# USB-RS485_A2.net
KiCad netlist of a schematic drawn in Altium Designer
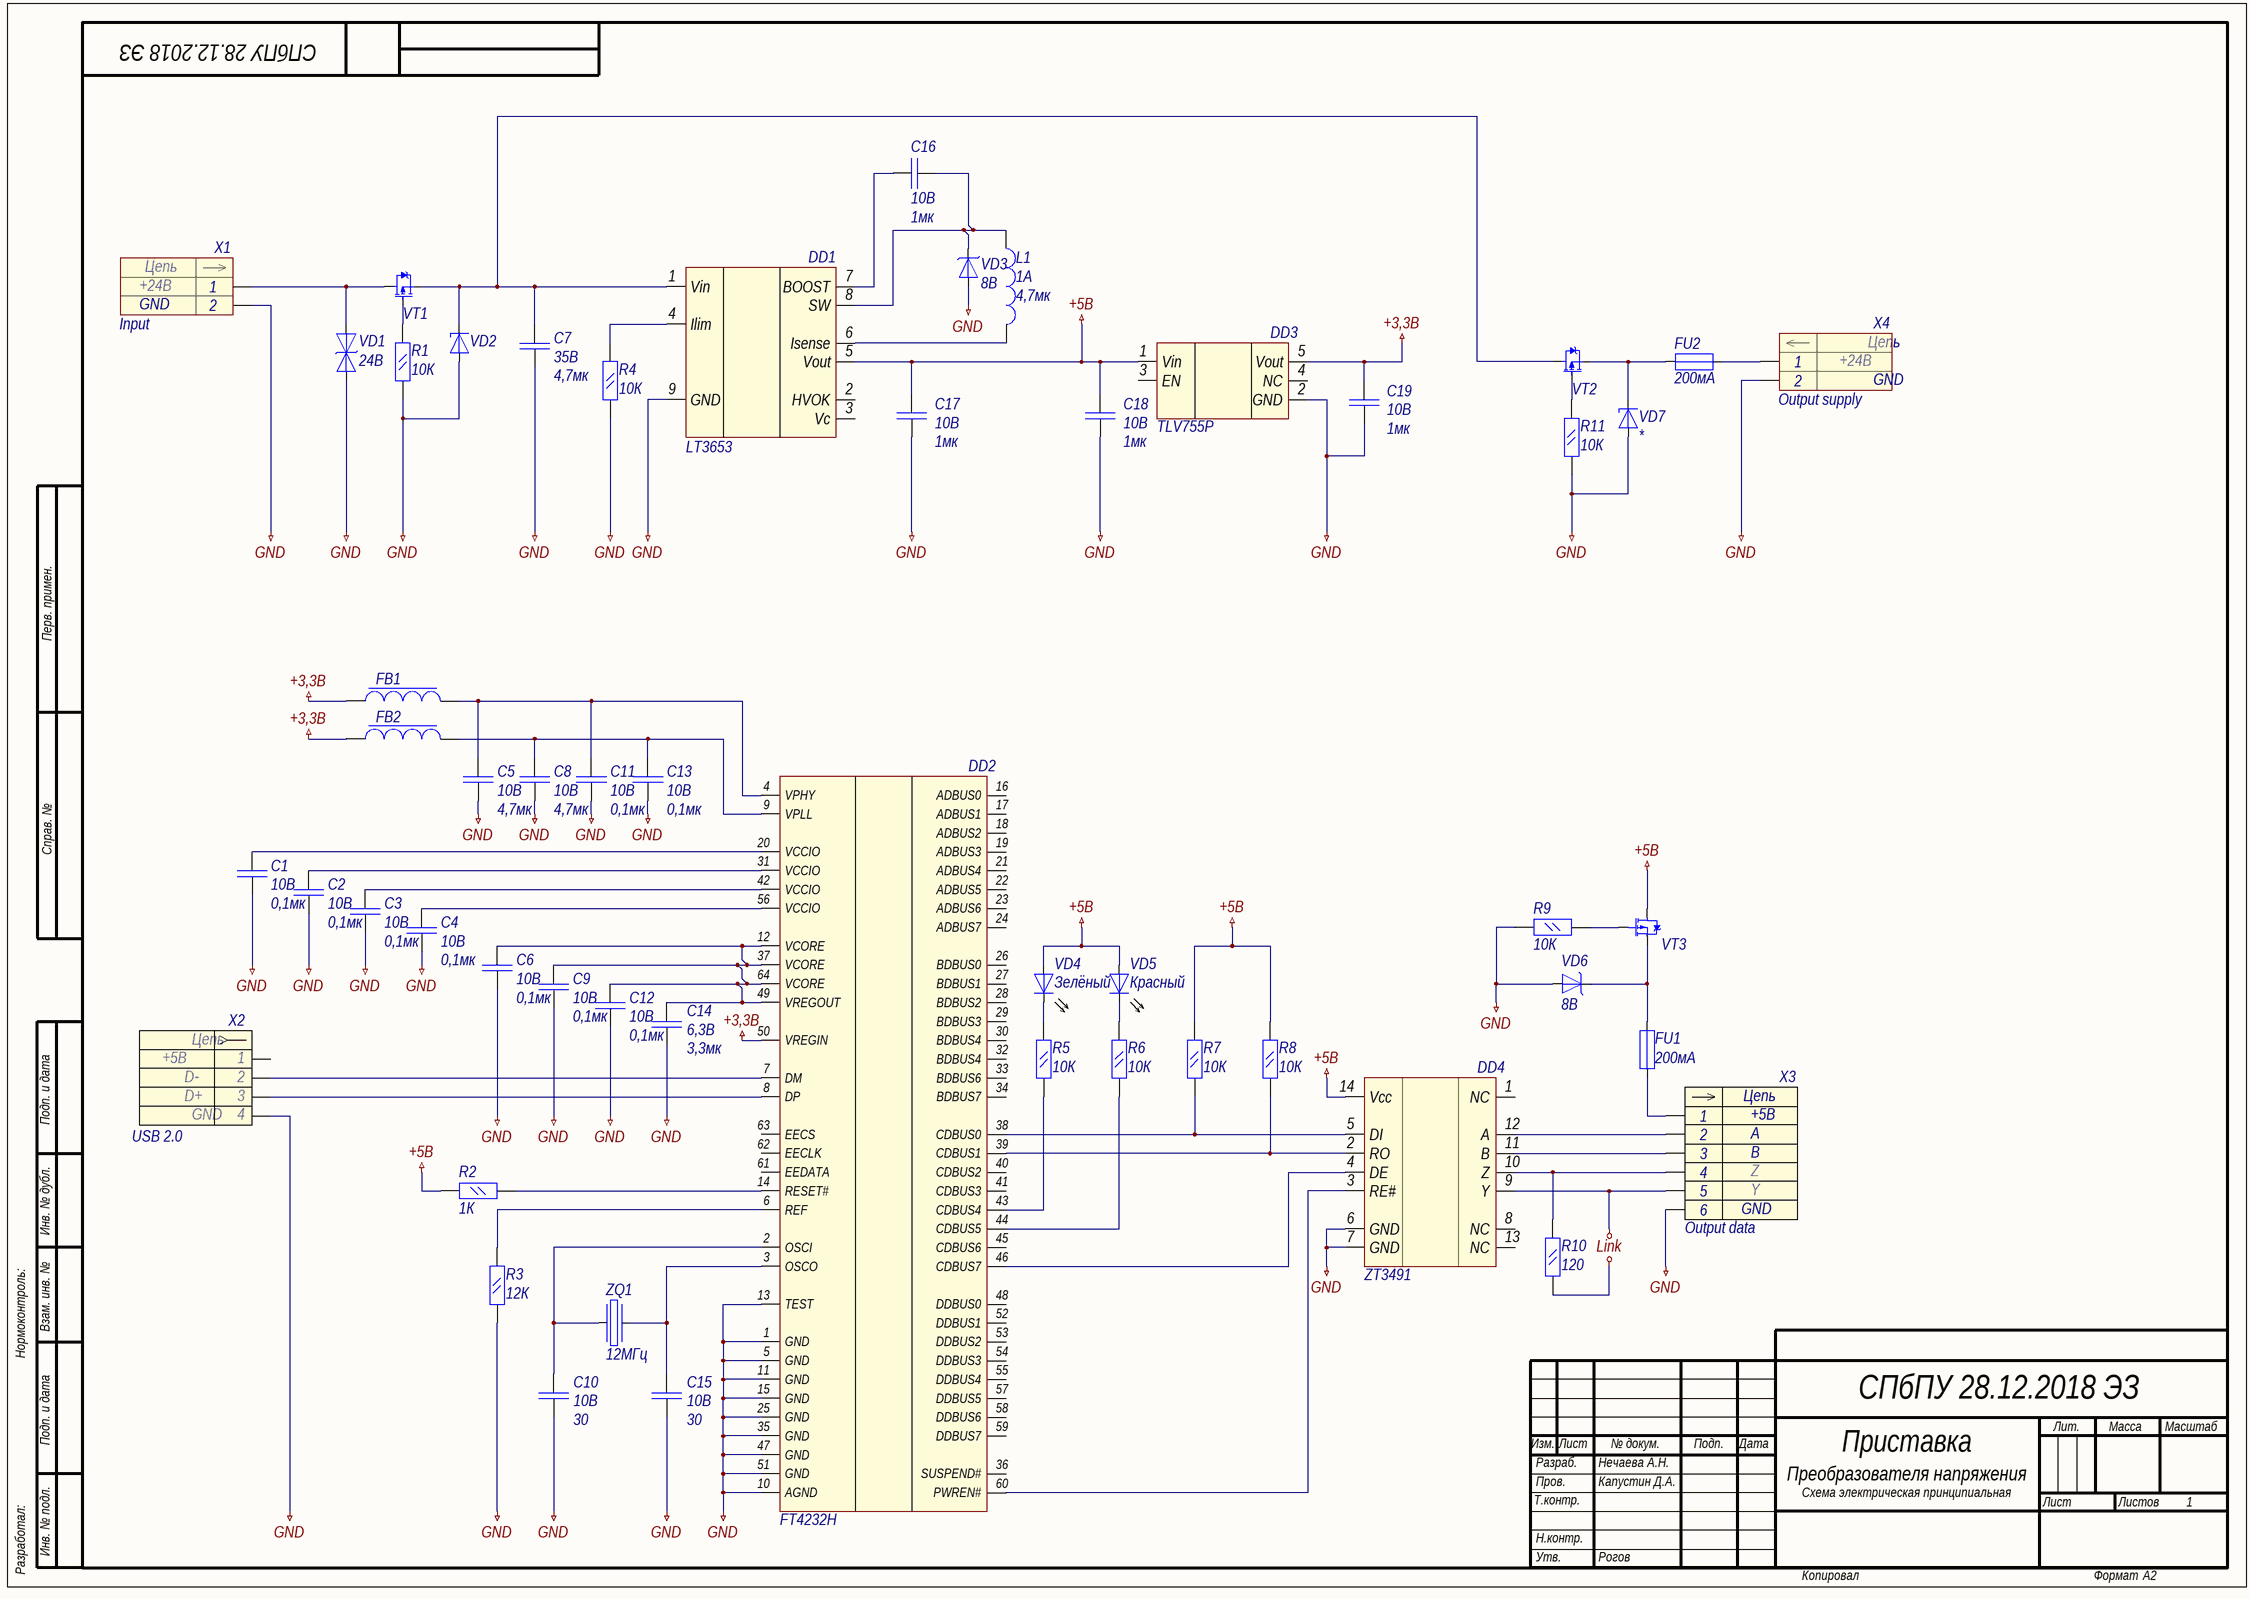
[diagram p0: USB-RS485_A2.SchDoc]

(export (version "E")
  (design (tool "Eeschema 10.0.6"))
  (components
    (comp (ref "C1")
      (value "Capacitor")
      (footprint "CH0402C")
      (fields (field (name "VOLTAGE") "10В") (field (name "CAPACITANCE") "0,1мк"))
      (libsource (lib "GOST_Capacitors") (part "Capacitor"))
    )
    (comp (ref "C2")
      (value "Capacitor")
      (footprint "CH0402C")
      (fields (field (name "VOLTAGE") "10В") (field (name "CAPACITANCE") "0,1мк"))
      (libsource (lib "GOST_Capacitors") (part "Capacitor"))
    )
    (comp (ref "C3")
      (value "Capacitor")
      (footprint "CH0402C")
      (fields (field (name "VOLTAGE") "10В") (field (name "CAPACITANCE") "0,1мк"))
      (libsource (lib "GOST_Capacitors") (part "Capacitor"))
    )
    (comp (ref "C4")
      (value "Capacitor")
      (footprint "CH0402C")
      (fields (field (name "VOLTAGE") "10В") (field (name "CAPACITANCE") "0,1мк"))
      (libsource (lib "GOST_Capacitors") (part "Capacitor"))
    )
    (comp (ref "C5")
      (value "Capacitor")
      (footprint "CH0402C")
      (fields (field (name "VOLTAGE") "10В") (field (name "CAPACITANCE") "4,7мк"))
      (libsource (lib "GOST_Capacitors") (part "Capacitor"))
    )
    (comp (ref "C6")
      (value "Capacitor")
      (footprint "CH0402C")
      (fields (field (name "VOLTAGE") "10В") (field (name "CAPACITANCE") "0,1мк"))
      (libsource (lib "GOST_Capacitors") (part "Capacitor"))
    )
    (comp (ref "C7")
      (value "Capacitor")
      (footprint "CH0603C")
      (fields (field (name "VOLTAGE") "35В") (field (name "CAPACITANCE") "4,7мк"))
      (libsource (lib "GOST_Capacitors") (part "Capacitor"))
    )
    (comp (ref "C8")
      (value "Capacitor")
      (footprint "CH0402C")
      (fields (field (name "VOLTAGE") "10В") (field (name "CAPACITANCE") "4,7мк"))
      (libsource (lib "GOST_Capacitors") (part "Capacitor"))
    )
    (comp (ref "C9")
      (value "Capacitor")
      (footprint "CH0402C")
      (fields (field (name "VOLTAGE") "10В") (field (name "CAPACITANCE") "0,1мк"))
      (libsource (lib "GOST_Capacitors") (part "Capacitor"))
    )
    (comp (ref "C10")
      (value "Capacitor")
      (footprint "CH0201C")
      (fields (field (name "VOLTAGE") "10В") (field (name "CAPACITANCE") "30"))
      (libsource (lib "GOST_Capacitors") (part "Capacitor"))
    )
    (comp (ref "C11")
      (value "Capacitor")
      (footprint "CH0402C")
      (fields (field (name "VOLTAGE") "10В") (field (name "CAPACITANCE") "0,1мк"))
      (libsource (lib "GOST_Capacitors") (part "Capacitor"))
    )
    (comp (ref "C12")
      (value "Capacitor")
      (footprint "CH0402C")
      (fields (field (name "VOLTAGE") "10В") (field (name "CAPACITANCE") "0,1мк"))
      (libsource (lib "GOST_Capacitors") (part "Capacitor"))
    )
    (comp (ref "C13")
      (value "Capacitor")
      (footprint "CH0402C")
      (fields (field (name "VOLTAGE") "10В") (field (name "CAPACITANCE") "0,1мк"))
      (libsource (lib "GOST_Capacitors") (part "Capacitor"))
    )
    (comp (ref "C14")
      (value "Capacitor")
      (footprint "CH0402C")
      (fields (field (name "VOLTAGE") "6,3В") (field (name "CAPACITANCE") "3,3мк"))
      (libsource (lib "GOST_Capacitors") (part "Capacitor"))
    )
    (comp (ref "C15")
      (value "Capacitor")
      (footprint "CH0201C")
      (fields (field (name "VOLTAGE") "10В") (field (name "CAPACITANCE") "30"))
      (libsource (lib "GOST_Capacitors") (part "Capacitor"))
    )
    (comp (ref "C16")
      (value "Capacitor")
      (footprint "CH0201C")
      (fields (field (name "VOLTAGE") "10В") (field (name "CAPACITANCE") "1мк"))
      (libsource (lib "GOST_Capacitors") (part "Capacitor"))
    )
    (comp (ref "C17")
      (value "Capacitor")
      (footprint "CH0201C")
      (fields (field (name "VOLTAGE") "10В") (field (name "CAPACITANCE") "1мк"))
      (libsource (lib "GOST_Capacitors") (part "Capacitor"))
    )
    (comp (ref "C18")
      (value "Capacitor")
      (footprint "CH0201C")
      (fields (field (name "VOLTAGE") "10В") (field (name "CAPACITANCE") "1мк"))
      (libsource (lib "GOST_Capacitors") (part "Capacitor"))
    )
    (comp (ref "C19")
      (value "Capacitor")
      (footprint "CH0201C")
      (fields (field (name "VOLTAGE") "10В") (field (name "CAPACITANCE") "1мк"))
      (libsource (lib "GOST_Capacitors") (part "Capacitor"))
    )
    (comp (ref "DD1")
      (value "LT3653")
      (footprint "LT3653")
      (description "7.5~30 to 5")
      (libsource (lib "GOST_lib_devices") (part "LT3653"))
    )
    (comp (ref "DD2")
      (value "FT4232H")
      (footprint "FT4232")
      (description "Ann")
      (libsource (lib "GOST_lib_devices") (part "FT4232H"))
    )
    (comp (ref "DD3")
      (value "TLV755P")
      (footprint "SOT23-5")
      (libsource (lib "GOST_lib_devices") (part "LDO +3.3V"))
    )
    (comp (ref "DD4")
      (value "ZT3491")
      (footprint "ZT3485E")
      (description "UART - RS485")
      (libsource (lib "GOST_lib_devices") (part "ZT3491"))
    )
    (comp (ref "FB1")
      (value "Ferrite bead")
      (footprint "CH0805F")
      (libsource (lib "GOST_Inductors") (part "Ferrite bead"))
    )
    (comp (ref "FB2")
      (value "Ferrite bead")
      (footprint "CH0805F")
      (libsource (lib "GOST_Inductors") (part "Ferrite bead"))
    )
    (comp (ref "FU1")
      (value "200мА")
      (footprint "CH0402R")
      (fields (field (name "Comment") "Fuse"))
      (libsource (lib "") (part "Fuse_1"))
    )
    (comp (ref "FU2")
      (value "200мА")
      (footprint "CH0402R")
      (fields (field (name "Comment") "Fuse"))
      (libsource (lib "GOST_Miscelanuious") (part "Fuse"))
    )
    (comp (ref "L1")
      (value "Inductor")
      (footprint "CH0805L")
      (fields (field (name "MAX CURRENT") "1А") (field (name "INDUCTANCE") "4,7мк"))
      (libsource (lib "GOST_Inductors") (part "Inductor"))
    )
    (comp (ref "R1")
      (value "Res_0.125")
      (footprint "CH0402R")
      (fields (field (name "IMPEDANCE") "10К"))
      (libsource (lib "GOST_Resistors") (part "Res_0.125"))
    )
    (comp (ref "R2")
      (value "Res_0.125")
      (footprint "CH0402R")
      (fields (field (name "IMPEDANCE") "1К"))
      (libsource (lib "GOST_Resistors") (part "Res_0.125"))
    )
    (comp (ref "R3")
      (value "Res_0.125")
      (footprint "CH0805R")
      (fields (field (name "IMPEDANCE") "12К"))
      (libsource (lib "GOST_Resistors") (part "Res_0.125"))
    )
    (comp (ref "R4")
      (value "Res_0.125")
      (footprint "CH0402R")
      (fields (field (name "IMPEDANCE") "10К"))
      (libsource (lib "GOST_Resistors") (part "Res_0.125"))
    )
    (comp (ref "R5")
      (value "Res_0.125")
      (footprint "CH0402R")
      (fields (field (name "IMPEDANCE") "10К"))
      (libsource (lib "GOST_Resistors") (part "Res_0.125"))
    )
    (comp (ref "R6")
      (value "Res_0.125")
      (footprint "CH0402R")
      (fields (field (name "IMPEDANCE") "10К"))
      (libsource (lib "GOST_Resistors") (part "Res_0.125"))
    )
    (comp (ref "R7")
      (value "Res_0.125")
      (footprint "CH0402R")
      (fields (field (name "IMPEDANCE") "10К"))
      (libsource (lib "GOST_Resistors") (part "Res_0.125"))
    )
    (comp (ref "R8")
      (value "Res_0.125")
      (footprint "CH0402R")
      (fields (field (name "IMPEDANCE") "10К"))
      (libsource (lib "GOST_Resistors") (part "Res_0.125"))
    )
    (comp (ref "R9")
      (value "Res_0.125")
      (footprint "CH0402R")
      (fields (field (name "IMPEDANCE") "10К"))
      (libsource (lib "GOST_Resistors") (part "Res_0.125"))
    )
    (comp (ref "R10")
      (value "Res_0.125")
      (footprint "CH0402R")
      (fields (field (name "IMPEDANCE") "120"))
      (libsource (lib "GOST_Resistors") (part "Res_0.125"))
    )
    (comp (ref "R11")
      (value "Res_0.125")
      (footprint "CH0402R")
      (fields (field (name "IMPEDANCE") "10К"))
      (libsource (lib "GOST_Resistors") (part "Res_0.125"))
    )
    (comp (ref "VD1")
      (value "TVS-diod_simmetrical")
      (footprint "standard:SOD323")
      (fields (field (name "MANUFACTURER") "Torex Semiconductor") (field (name "THRESH_VOLTAGE") "24В"))
      (libsource (lib "GOST_Diodes") (part "TVS-diod_simmetrical"))
    )
    (comp (ref "VD2")
      (value "Diod Zener")
      (footprint "standard:SOD123")
      (libsource (lib "GOST_Diodes") (part "Diod Zener"))
    )
    (comp (ref "VD3")
      (value "TVS-diod_directed")
      (footprint "SOD123W")
      (fields (field (name "MANUFACTURER") "Nexperia") (field (name "CLAMPING_VOLTAGE") "8В"))
      (libsource (lib "GOST_Diodes") (part "TVS-diod_directed"))
    )
    (comp (ref "VD4")
      (value "Light_diod")
      (footprint "CH0201L")
      (fields (field (name "COLOR") "Зелёный"))
      (libsource (lib "GOST_Diodes") (part "Light_diod"))
    )
    (comp (ref "VD5")
      (value "Light_diod")
      (footprint "CH0201L")
      (fields (field (name "COLOR") "Красный"))
      (libsource (lib "GOST_Diodes") (part "Light_diod"))
    )
    (comp (ref "VD6")
      (value "TVS-diod_directed")
      (footprint "SOD123W")
      (fields (field (name "MANUFACTURER") "Nexperia") (field (name "CLAMPING_VOLTAGE") "8В"))
      (libsource (lib "GOST_Diodes") (part "TVS-diod_directed"))
    )
    (comp (ref "VD7")
      (value "Diod Zener")
      (footprint "standard:SOD123")
      (fields (field (name "THRESH_VOLTAGE") "*"))
      (libsource (lib "GOST_Diodes") (part "Diod Zener"))
    )
    (comp (ref "VT1")
      (value "P-Channel")
      (footprint "SOT23_132")
      (libsource (lib "GOST_Transistors") (part "P-Channel"))
    )
    (comp (ref "VT2")
      (value "P-Channel")
      (footprint "SOT23_132")
      (libsource (lib "GOST_Transistors") (part "P-Channel"))
    )
    (comp (ref "VT3") (value "*") (footprint "SOT23_132") (libsource (lib "") (part "P-Channel_1")))
    (comp (ref "X1")
      (value "Input")
      (footprint "CON: 163-179PH-EX")
      (fields (field (name "VCC") "+24В"))
      (libsource (lib "GOST_lib_connectors") (part "2_pins"))
    )
    (comp (ref "X2")
      (value "USB 2.0")
      (footprint "Integrated_Library:USB")
      (description "USB")
      (fields (field (name "MANUFACTURER") "TE Connectivity") (field (name "VCC") "+5В"))
      (libsource (lib "Connectors") (part "USB-A"))
    )
    (comp (ref "X3")
      (value "Output data")
      (footprint "CON: PBS-6")
      (fields
        (field (name "Z") "Z")
        (field (name "Y") "Y")
        (field (name "VCC") "+5В")
        (field (name "A") "A")
        (field (name "B") "B")
      )
      (libsource (lib "GOST_lib_connectors") (part "Full_Duplex_RS485"))
    )
    (comp (ref "X4")
      (value "Output supply")
      (footprint "CON: PBS-2")
      (fields (field (name "VCC") "+24В"))
      (libsource (lib "") (part "2_pins_1"))
    )
    (comp (ref "ZQ1")
      (value "12МГц")
      (footprint "OSC: 5032")
      (fields (field (name "Comment") "Oscillator"))
      (libsource (lib "GOST_Miscelanuious") (part "Oscillator"))
    )
  )
  (nets
    (net (code "1") (name "+3,3В") (class "Default")
      (node (ref "C19") (pin "1") (pinfunction "C1+_1") (pintype "power_in"))
      (node (ref "DD2") (pin "50") (pinfunction "VREGIN_50") (pintype "power_in"))
      (node (ref "DD3") (pin "5") (pinfunction "Vout_5") (pintype "power_in"))
      (node (ref "FB1") (pin "1") (pinfunction "C1-_1") (pintype "power_in"))
      (node (ref "FB2") (pin "1") (pinfunction "C1-_1") (pintype "power_in"))
    )
    (net (code "2") (name "+5В") (class "Default")
      (node (ref "C17") (pin "1") (pinfunction "C1+_1") (pintype "power_in"))
      (node (ref "C18") (pin "1") (pinfunction "C1+_1") (pintype "power_in"))
      (node (ref "DD1") (pin "5") (pinfunction "Vout_5") (pintype "power_in"))
      (node (ref "DD3") (pin "1") (pinfunction "Vin_1") (pintype "power_in"))
      (node (ref "DD4") (pin "14") (pinfunction "Vcc_14") (pintype "power_in"))
      (node (ref "R2") (pin "2") (pinfunction "2_2") (pintype "power_in"))
      (node (ref "R7") (pin "2") (pinfunction "2_2") (pintype "power_in"))
      (node (ref "R8") (pin "2") (pinfunction "2_2") (pintype "power_in"))
      (node (ref "VD4") (pin "1") (pinfunction "1_1") (pintype "passive"))
      (node (ref "VD5") (pin "1") (pinfunction "1_1") (pintype "passive"))
      (node (ref "VT3") (pin "2") (pinfunction "D_2") (pintype "passive"))
    )
    (net (code "3") (name "GND") (class "Default")
      (node (ref "C1") (pin "2") (pinfunction "C1-_2") (pintype "power_in"))
      (node (ref "C10") (pin "2") (pinfunction "C1-_2") (pintype "power_in"))
      (node (ref "C11") (pin "2") (pinfunction "C1-_2") (pintype "power_in"))
      (node (ref "C12") (pin "2") (pinfunction "C1-_2") (pintype "power_in"))
      (node (ref "C13") (pin "2") (pinfunction "C1-_2") (pintype "power_in"))
      (node (ref "C14") (pin "2") (pinfunction "C1-_2") (pintype "power_in"))
      (node (ref "C15") (pin "2") (pinfunction "C1-_2") (pintype "power_in"))
      (node (ref "C17") (pin "2") (pinfunction "C1-_2") (pintype "power_in"))
      (node (ref "C18") (pin "2") (pinfunction "C1-_2") (pintype "power_in"))
      (node (ref "C19") (pin "2") (pinfunction "C1-_2") (pintype "power_in"))
      (node (ref "C2") (pin "2") (pinfunction "C1-_2") (pintype "power_in"))
      (node (ref "C3") (pin "2") (pinfunction "C1-_2") (pintype "power_in"))
      (node (ref "C4") (pin "2") (pinfunction "C1-_2") (pintype "power_in"))
      (node (ref "C5") (pin "2") (pinfunction "C1-_2") (pintype "power_in"))
      (node (ref "C6") (pin "2") (pinfunction "C1-_2") (pintype "power_in"))
      (node (ref "C7") (pin "2") (pinfunction "C1-_2") (pintype "power_in"))
      (node (ref "C8") (pin "2") (pinfunction "C1-_2") (pintype "power_in"))
      (node (ref "C9") (pin "2") (pinfunction "C1-_2") (pintype "power_in"))
      (node (ref "DD1") (pin "9") (pinfunction "GND_9") (pintype "power_in"))
      (node (ref "DD2") (pin "1") (pinfunction "GND_1") (pintype "power_in"))
      (node (ref "DD2") (pin "10") (pinfunction "AGND_10") (pintype "power_in"))
      (node (ref "DD2") (pin "11") (pinfunction "GND_11") (pintype "power_in"))
      (node (ref "DD2") (pin "13") (pinfunction "TEST_13") (pintype "power_in"))
      (node (ref "DD2") (pin "15") (pinfunction "GND_15") (pintype "power_in"))
      (node (ref "DD2") (pin "25") (pinfunction "GND_25") (pintype "power_in"))
      (node (ref "DD2") (pin "35") (pinfunction "GND_35") (pintype "power_in"))
      (node (ref "DD2") (pin "47") (pinfunction "GND_47") (pintype "power_in"))
      (node (ref "DD2") (pin "5") (pinfunction "GND_5") (pintype "power_in"))
      (node (ref "DD2") (pin "51") (pinfunction "GND_51") (pintype "power_in"))
      (node (ref "DD3") (pin "2") (pinfunction "GND_2") (pintype "power_in"))
      (node (ref "DD4") (pin "6") (pinfunction "GND_6") (pintype "power_in"))
      (node (ref "DD4") (pin "7") (pinfunction "GND_7") (pintype "power_in"))
      (node (ref "R1") (pin "1") (pinfunction "1_1") (pintype "power_in"))
      (node (ref "R11") (pin "1") (pinfunction "1_1") (pintype "power_in"))
      (node (ref "R3") (pin "1") (pinfunction "1_1") (pintype "power_in"))
      (node (ref "R4") (pin "1") (pinfunction "1_1") (pintype "power_in"))
      (node (ref "R9") (pin "2") (pinfunction "2_2") (pintype "power_in"))
      (node (ref "VD1") (pin "1") (pinfunction "A_1") (pintype "passive"))
      (node (ref "VD2") (pin "1") (pinfunction "A_1") (pintype "passive"))
      (node (ref "VD3") (pin "1") (pinfunction "A_1") (pintype "passive"))
      (node (ref "VD6") (pin "1") (pinfunction "A_1") (pintype "passive"))
      (node (ref "VD7") (pin "1") (pinfunction "A_1") (pintype "passive"))
      (node (ref "X1") (pin "2") (pinfunction "2_2") (pintype "passive"))
      (node (ref "X2") (pin "4") (pinfunction "4_4") (pintype "passive"))
      (node (ref "X3") (pin "6") (pinfunction "6_6") (pintype "passive"))
      (node (ref "X4") (pin "2") (pinfunction "2_2") (pintype "passive"))
    )
    (net (code "4") (name "Link") (class "Default")
      (node (ref "DD4") (pin "9") (pinfunction "Y_9") (pintype "power_in"))
      (node (ref "R10") (pin "1") (pinfunction "1_1") (pintype "power_in"))
      (node (ref "X3") (pin "5") (pinfunction "5_5") (pintype "passive"))
    )
    (net (code "5") (name "Net-(C1-C1+)") (class "Default")
      (node (ref "C1") (pin "1") (pinfunction "C1+_1") (pintype "power_in"))
      (node (ref "DD2") (pin "20") (pinfunction "VCCIO_20") (pintype "power_in"))
    )
    (net (code "6") (name "Net-(C2-C1+)") (class "Default")
      (node (ref "C2") (pin "1") (pinfunction "C1+_1") (pintype "power_in"))
      (node (ref "DD2") (pin "31") (pinfunction "VCCIO_31") (pintype "power_in"))
    )
    (net (code "7") (name "Net-(C3-C1+)") (class "Default")
      (node (ref "C3") (pin "1") (pinfunction "C1+_1") (pintype "power_in"))
      (node (ref "DD2") (pin "42") (pinfunction "VCCIO_42") (pintype "power_in"))
    )
    (net (code "8") (name "Net-(C4-C1+)") (class "Default")
      (node (ref "C4") (pin "1") (pinfunction "C1+_1") (pintype "power_in"))
      (node (ref "DD2") (pin "56") (pinfunction "VCCIO_56") (pintype "power_in"))
    )
    (net (code "9") (name "Net-(C7-C1+)") (class "Default")
      (node (ref "C7") (pin "1") (pinfunction "C1+_1") (pintype "power_in"))
      (node (ref "DD1") (pin "1") (pinfunction "Vin_1") (pintype "power_in"))
      (node (ref "VD2") (pin "2") (pinfunction "C_2") (pintype "passive"))
      (node (ref "VT1") (pin "3") (pinfunction "S_3") (pintype "passive"))
      (node (ref "VT2") (pin "2") (pinfunction "D_2") (pintype "passive"))
    )
    (net (code "10") (name "Net-(C10-C1+)") (class "Default")
      (node (ref "C10") (pin "1") (pinfunction "C1+_1") (pintype "power_in"))
      (node (ref "DD2") (pin "2") (pinfunction "OSCI_2") (pintype "power_in"))
      (node (ref "ZQ1") (pin "1") (pinfunction "1_1") (pintype "passive"))
    )
    (net (code "11") (name "Net-(C11-C1+)") (class "Default")
      (node (ref "C11") (pin "1") (pinfunction "C1+_1") (pintype "power_in"))
      (node (ref "C5") (pin "1") (pinfunction "C1+_1") (pintype "power_in"))
      (node (ref "DD2") (pin "4") (pinfunction "VPHY_4") (pintype "power_in"))
      (node (ref "FB1") (pin "2") (pinfunction "14_2") (pintype "power_in"))
    )
    (net (code "12") (name "Net-(C12-C1+)") (class "Default")
      (node (ref "C12") (pin "1") (pinfunction "C1+_1") (pintype "power_in"))
      (node (ref "C14") (pin "1") (pinfunction "C1+_1") (pintype "power_in"))
      (node (ref "C6") (pin "1") (pinfunction "C1+_1") (pintype "power_in"))
      (node (ref "C9") (pin "1") (pinfunction "C1+_1") (pintype "power_in"))
      (node (ref "DD2") (pin "12") (pinfunction "VCORE_12") (pintype "power_in"))
      (node (ref "DD2") (pin "37") (pinfunction "VCORE_37") (pintype "power_in"))
      (node (ref "DD2") (pin "49") (pinfunction "VREGOUT_49") (pintype "power_in"))
      (node (ref "DD2") (pin "64") (pinfunction "VCORE_64") (pintype "power_in"))
    )
    (net (code "13") (name "Net-(C13-C1+)") (class "Default")
      (node (ref "C13") (pin "1") (pinfunction "C1+_1") (pintype "power_in"))
      (node (ref "C8") (pin "1") (pinfunction "C1+_1") (pintype "power_in"))
      (node (ref "DD2") (pin "9") (pinfunction "VPLL_9") (pintype "power_in"))
      (node (ref "FB2") (pin "2") (pinfunction "14_2") (pintype "power_in"))
    )
    (net (code "14") (name "Net-(C15-C1+)") (class "Default")
      (node (ref "C15") (pin "1") (pinfunction "C1+_1") (pintype "power_in"))
      (node (ref "DD2") (pin "3") (pinfunction "OSCO_3") (pintype "power_in"))
      (node (ref "ZQ1") (pin "3") (pinfunction "3_3") (pintype "passive"))
    )
    (net (code "15") (name "Net-(C16-C1+)") (class "Default")
      (node (ref "C16") (pin "1") (pinfunction "C1+_1") (pintype "power_in"))
      (node (ref "DD1") (pin "7") (pinfunction "BOOST_7") (pintype "power_in"))
    )
    (net (code "16") (name "Net-(C16-C1-)") (class "Default")
      (node (ref "C16") (pin "2") (pinfunction "C1-_2") (pintype "power_in"))
      (node (ref "DD1") (pin "8") (pinfunction "SW_8") (pintype "power_in"))
      (node (ref "L1") (pin "1") (pinfunction "1_1") (pintype "power_in"))
      (node (ref "VD3") (pin "2") (pinfunction "C_2") (pintype "passive"))
    )
    (net (code "17") (name "Net-(DD1-Ilim)") (class "Default")
      (node (ref "DD1") (pin "4") (pinfunction "Ilim_4") (pintype "power_in"))
      (node (ref "R4") (pin "2") (pinfunction "2_2") (pintype "power_in"))
    )
    (net (code "18") (name "Net-(DD1-Isense)") (class "Default")
      (node (ref "DD1") (pin "6") (pinfunction "Isense_6") (pintype "power_in"))
      (node (ref "L1") (pin "2") (pinfunction "2_2") (pintype "power_in"))
    )
    (net (code "19") (name "Net-(DD2-CDBUS0)") (class "Default")
      (node (ref "DD2") (pin "38") (pinfunction "CDBUS0_38") (pintype "power_in"))
      (node (ref "DD4") (pin "5") (pinfunction "DI_5") (pintype "power_in"))
      (node (ref "R7") (pin "1") (pinfunction "1_1") (pintype "power_in"))
    )
    (net (code "20") (name "Net-(DD2-CDBUS1)") (class "Default")
      (node (ref "DD2") (pin "39") (pinfunction "CDBUS1_39") (pintype "power_in"))
      (node (ref "DD4") (pin "2") (pinfunction "RO_2") (pintype "power_in"))
      (node (ref "R8") (pin "1") (pinfunction "1_1") (pintype "power_in"))
    )
    (net (code "21") (name "Net-(DD2-CDBUS4)") (class "Default")
      (node (ref "DD2") (pin "43") (pinfunction "CDBUS4_43") (pintype "power_in"))
      (node (ref "R5") (pin "1") (pinfunction "1_1") (pintype "power_in"))
    )
    (net (code "22") (name "Net-(DD2-CDBUS5)") (class "Default")
      (node (ref "DD2") (pin "44") (pinfunction "CDBUS5_44") (pintype "power_in"))
      (node (ref "R6") (pin "1") (pinfunction "1_1") (pintype "power_in"))
    )
    (net (code "23") (name "Net-(DD2-CDBUS7)") (class "Default")
      (node (ref "DD2") (pin "46") (pinfunction "CDBUS7_46") (pintype "power_in"))
      (node (ref "DD4") (pin "4") (pinfunction "DE_4") (pintype "power_in"))
    )
    (net (code "24") (name "Net-(DD2-DM)") (class "Default")
      (node (ref "DD2") (pin "7") (pinfunction "DM_7") (pintype "power_in"))
      (node (ref "X2") (pin "2") (pinfunction "2_2") (pintype "passive"))
    )
    (net (code "25") (name "Net-(DD2-DP)") (class "Default")
      (node (ref "DD2") (pin "8") (pinfunction "DP_8") (pintype "power_in"))
      (node (ref "X2") (pin "3") (pinfunction "3_3") (pintype "passive"))
    )
    (net (code "26") (name "Net-(DD2-PWREN#)") (class "Default")
      (node (ref "DD2") (pin "60") (pinfunction "PWREN#_60") (pintype "power_in"))
      (node (ref "DD4") (pin "3") (pinfunction "RE#_3") (pintype "power_in"))
    )
    (net (code "27") (name "Net-(DD2-REF)") (class "Default")
      (node (ref "DD2") (pin "6") (pinfunction "REF_6") (pintype "power_in"))
      (node (ref "R3") (pin "2") (pinfunction "2_2") (pintype "power_in"))
    )
    (net (code "28") (name "Net-(DD2-RESET#)") (class "Default")
      (node (ref "DD2") (pin "14") (pinfunction "RESET#_14") (pintype "power_in"))
      (node (ref "R2") (pin "1") (pinfunction "1_1") (pintype "power_in"))
    )
    (net (code "29") (name "Net-(DD4-A)") (class "Default")
      (node (ref "DD4") (pin "12") (pinfunction "A_12") (pintype "power_in"))
      (node (ref "X3") (pin "2") (pinfunction "2_2") (pintype "passive"))
    )
    (net (code "30") (name "Net-(DD4-B)") (class "Default")
      (node (ref "DD4") (pin "11") (pinfunction "B_11") (pintype "power_in"))
      (node (ref "X3") (pin "3") (pinfunction "3_3") (pintype "passive"))
    )
    (net (code "31") (name "Net-(DD4-Z)") (class "Default")
      (node (ref "DD4") (pin "10") (pinfunction "Z_10") (pintype "power_in"))
      (node (ref "R10") (pin "2") (pinfunction "2_2") (pintype "power_in"))
      (node (ref "X3") (pin "4") (pinfunction "4_4") (pintype "passive"))
    )
    (net (code "32") (name "Net-(FU1-Pad1)") (class "Default")
      (node (ref "FU1") (pin "1") (pinfunction "1_1") (pintype "passive"))
      (node (ref "X3") (pin "1") (pinfunction "1_1") (pintype "passive"))
    )
    (net (code "33") (name "Net-(FU2-Pad2)") (class "Default")
      (node (ref "FU2") (pin "2") (pinfunction "2_2") (pintype "passive"))
      (node (ref "X4") (pin "1") (pinfunction "1_1") (pintype "passive"))
    )
    (net (code "34") (name "Net-(R5-Pad2)") (class "Default")
      (node (ref "R5") (pin "2") (pinfunction "2_2") (pintype "power_in"))
      (node (ref "VD4") (pin "2") (pinfunction "2_2") (pintype "passive"))
    )
    (net (code "35") (name "Net-(R6-Pad2)") (class "Default")
      (node (ref "R6") (pin "2") (pinfunction "2_2") (pintype "power_in"))
      (node (ref "VD5") (pin "2") (pinfunction "2_2") (pintype "passive"))
    )
    (net (code "36") (name "Net-(VD1-C)") (class "Default")
      (node (ref "VD1") (pin "2") (pinfunction "C_2") (pintype "passive"))
      (node (ref "VT1") (pin "2") (pinfunction "D_2") (pintype "passive"))
      (node (ref "X1") (pin "1") (pinfunction "1_1") (pintype "passive"))
    )
    (net (code "37") (name "Net-(VD6-C)") (class "Default")
      (node (ref "FU1") (pin "2") (pinfunction "2_2") (pintype "passive"))
      (node (ref "VD6") (pin "2") (pinfunction "C_2") (pintype "passive"))
      (node (ref "VT3") (pin "3") (pinfunction "S_3") (pintype "passive"))
    )
    (net (code "38") (name "Net-(VD7-C)") (class "Default")
      (node (ref "FU2") (pin "1") (pinfunction "1_1") (pintype "passive"))
      (node (ref "VD7") (pin "2") (pinfunction "C_2") (pintype "passive"))
      (node (ref "VT2") (pin "3") (pinfunction "S_3") (pintype "passive"))
    )
    (net (code "39") (name "Net-(VT1-G)") (class "Default")
      (node (ref "R1") (pin "2") (pinfunction "2_2") (pintype "power_in"))
      (node (ref "VT1") (pin "1") (pinfunction "G_1") (pintype "passive"))
    )
    (net (code "40") (name "Net-(VT2-G)") (class "Default")
      (node (ref "R11") (pin "2") (pinfunction "2_2") (pintype "power_in"))
      (node (ref "VT2") (pin "1") (pinfunction "G_1") (pintype "passive"))
    )
    (net (code "41") (name "Net-(VT3-G)") (class "Default")
      (node (ref "R9") (pin "1") (pinfunction "1_1") (pintype "power_in"))
      (node (ref "VT3") (pin "1") (pinfunction "G_1") (pintype "passive"))
    )
    (net (code "42") (name "unconnected-(DD1-HVOK-Pad2)") (class "Default")
      (node (ref "DD1") (pin "2") (pinfunction "HVOK_2") (pintype "power_in"))
    )
    (net (code "43") (name "unconnected-(DD1-Vc-Pad3)") (class "Default")
      (node (ref "DD1") (pin "3") (pinfunction "Vc_3") (pintype "power_in"))
    )
    (net (code "44") (name "unconnected-(DD2-ADBUS0-Pad16)") (class "Default")
      (node (ref "DD2") (pin "16") (pinfunction "ADBUS0_16") (pintype "power_in"))
    )
    (net (code "45") (name "unconnected-(DD2-ADBUS1-Pad17)") (class "Default")
      (node (ref "DD2") (pin "17") (pinfunction "ADBUS1_17") (pintype "power_in"))
    )
    (net (code "46") (name "unconnected-(DD2-ADBUS2-Pad18)") (class "Default")
      (node (ref "DD2") (pin "18") (pinfunction "ADBUS2_18") (pintype "power_in"))
    )
    (net (code "47") (name "unconnected-(DD2-ADBUS3-Pad19)") (class "Default")
      (node (ref "DD2") (pin "19") (pinfunction "ADBUS3_19") (pintype "power_in"))
    )
    (net (code "48") (name "unconnected-(DD2-ADBUS4-Pad21)") (class "Default")
      (node (ref "DD2") (pin "21") (pinfunction "ADBUS4_21") (pintype "power_in"))
    )
    (net (code "49") (name "unconnected-(DD2-ADBUS5-Pad22)") (class "Default")
      (node (ref "DD2") (pin "22") (pinfunction "ADBUS5_22") (pintype "power_in"))
    )
    (net (code "50") (name "unconnected-(DD2-ADBUS6-Pad23)") (class "Default")
      (node (ref "DD2") (pin "23") (pinfunction "ADBUS6_23") (pintype "power_in"))
    )
    (net (code "51") (name "unconnected-(DD2-ADBUS7-Pad24)") (class "Default")
      (node (ref "DD2") (pin "24") (pinfunction "ADBUS7_24") (pintype "power_in"))
    )
    (net (code "52") (name "unconnected-(DD2-BDBUS0-Pad26)") (class "Default")
      (node (ref "DD2") (pin "26") (pinfunction "BDBUS0_26") (pintype "power_in"))
    )
    (net (code "53") (name "unconnected-(DD2-BDBUS1-Pad27)") (class "Default")
      (node (ref "DD2") (pin "27") (pinfunction "BDBUS1_27") (pintype "power_in"))
    )
    (net (code "54") (name "unconnected-(DD2-BDBUS2-Pad28)") (class "Default")
      (node (ref "DD2") (pin "28") (pinfunction "BDBUS2_28") (pintype "power_in"))
    )
    (net (code "55") (name "unconnected-(DD2-BDBUS3-Pad29)") (class "Default")
      (node (ref "DD2") (pin "29") (pinfunction "BDBUS3_29") (pintype "power_in"))
    )
    (net (code "56") (name "unconnected-(DD2-BDBUS4-Pad30)") (class "Default")
      (node (ref "DD2") (pin "30") (pinfunction "BDBUS4_30") (pintype "power_in"))
    )
    (net (code "57") (name "unconnected-(DD2-BDBUS4-Pad32)") (class "Default")
      (node (ref "DD2") (pin "32") (pinfunction "BDBUS4_32") (pintype "power_in"))
    )
    (net (code "58") (name "unconnected-(DD2-BDBUS6-Pad33)") (class "Default")
      (node (ref "DD2") (pin "33") (pinfunction "BDBUS6_33") (pintype "power_in"))
    )
    (net (code "59") (name "unconnected-(DD2-BDBUS7-Pad34)") (class "Default")
      (node (ref "DD2") (pin "34") (pinfunction "BDBUS7_34") (pintype "power_in"))
    )
    (net (code "60") (name "unconnected-(DD2-CDBUS2-Pad40)") (class "Default")
      (node (ref "DD2") (pin "40") (pinfunction "CDBUS2_40") (pintype "power_in"))
    )
    (net (code "61") (name "unconnected-(DD2-CDBUS3-Pad41)") (class "Default")
      (node (ref "DD2") (pin "41") (pinfunction "CDBUS3_41") (pintype "power_in"))
    )
    (net (code "62") (name "unconnected-(DD2-CDBUS6-Pad45)") (class "Default")
      (node (ref "DD2") (pin "45") (pinfunction "CDBUS6_45") (pintype "power_in"))
    )
    (net (code "63") (name "unconnected-(DD2-DDBUS0-Pad48)") (class "Default")
      (node (ref "DD2") (pin "48") (pinfunction "DDBUS0_48") (pintype "power_in"))
    )
    (net (code "64") (name "unconnected-(DD2-DDBUS1-Pad52)") (class "Default")
      (node (ref "DD2") (pin "52") (pinfunction "DDBUS1_52") (pintype "power_in"))
    )
    (net (code "65") (name "unconnected-(DD2-DDBUS2-Pad53)") (class "Default")
      (node (ref "DD2") (pin "53") (pinfunction "DDBUS2_53") (pintype "power_in"))
    )
    (net (code "66") (name "unconnected-(DD2-DDBUS3-Pad54)") (class "Default")
      (node (ref "DD2") (pin "54") (pinfunction "DDBUS3_54") (pintype "power_in"))
    )
    (net (code "67") (name "unconnected-(DD2-DDBUS4-Pad55)") (class "Default")
      (node (ref "DD2") (pin "55") (pinfunction "DDBUS4_55") (pintype "power_in"))
    )
    (net (code "68") (name "unconnected-(DD2-DDBUS5-Pad57)") (class "Default")
      (node (ref "DD2") (pin "57") (pinfunction "DDBUS5_57") (pintype "power_in"))
    )
    (net (code "69") (name "unconnected-(DD2-DDBUS6-Pad58)") (class "Default")
      (node (ref "DD2") (pin "58") (pinfunction "DDBUS6_58") (pintype "power_in"))
    )
    (net (code "70") (name "unconnected-(DD2-DDBUS7-Pad59)") (class "Default")
      (node (ref "DD2") (pin "59") (pinfunction "DDBUS7_59") (pintype "power_in"))
    )
    (net (code "71") (name "unconnected-(DD2-EECLK-Pad62)") (class "Default")
      (node (ref "DD2") (pin "62") (pinfunction "EECLK_62") (pintype "power_in"))
    )
    (net (code "72") (name "unconnected-(DD2-EECS-Pad63)") (class "Default")
      (node (ref "DD2") (pin "63") (pinfunction "EECS_63") (pintype "power_in"))
    )
    (net (code "73") (name "unconnected-(DD2-EEDATA-Pad61)") (class "Default")
      (node (ref "DD2") (pin "61") (pinfunction "EEDATA_61") (pintype "power_in"))
    )
    (net (code "74") (name "unconnected-(DD2-SUSPEND#-Pad36)") (class "Default")
      (node (ref "DD2") (pin "36") (pinfunction "SUSPEND#_36") (pintype "power_in"))
    )
    (net (code "75") (name "unconnected-(DD3-EN-Pad3)") (class "Default")
      (node (ref "DD3") (pin "3") (pinfunction "EN_3") (pintype "power_in"))
    )
    (net (code "76") (name "unconnected-(DD3-NC-Pad4)") (class "Default")
      (node (ref "DD3") (pin "4") (pinfunction "NC_4") (pintype "power_in"))
    )
    (net (code "77") (name "unconnected-(DD4-NC-Pad1)") (class "Default")
      (node (ref "DD4") (pin "1") (pinfunction "NC_1") (pintype "power_in"))
    )
    (net (code "78") (name "unconnected-(DD4-NC-Pad8)") (class "Default")
      (node (ref "DD4") (pin "8") (pinfunction "NC_8") (pintype "power_in"))
    )
    (net (code "79") (name "unconnected-(DD4-NC-Pad13)") (class "Default")
      (node (ref "DD4") (pin "13") (pinfunction "NC_13") (pintype "power_in"))
    )
    (net (code "80") (name "unconnected-(X2-Pad1)") (class "Default")
      (node (ref "X2") (pin "1") (pintype "passive"))
    )
  )
)
